# PhotoSensor.net
KiCad netlist of a schematic drawn in EAGLE
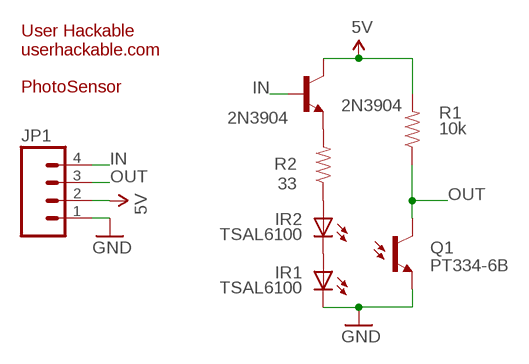
[diagram p0: schematic, sheet 1]

(export (version "E")
  (design (tool "Eeschema 10.0.6"))
  (components
    (comp (ref "2N3904")
      (value "2N3904")
      (footprint "eagle-import:TO-92-AMMO")
      (libsource (lib "eagle-import") (part "TRANSISTOR_NPNTO-92-AMMO"))
    )
    (comp (ref "IR1")
      (value "TSAL6100")
      (footprint "eagle-import:LED5MM")
      (libsource (lib "eagle-import") (part "LED5MM"))
    )
    (comp (ref "IR2")
      (value "TSAL6100")
      (footprint "eagle-import:LED5MM")
      (libsource (lib "eagle-import") (part "LED5MM"))
    )
    (comp (ref "JP1")
      (value "M04PTH")
      (footprint "eagle-import:1X04")
      (libsource (lib "eagle-import") (part "M04PTH"))
    )
    (comp (ref "Q1")
      (value "PT334-6B")
      (footprint "eagle-import:LED5MM")
      (libsource (lib "eagle-import") (part "PHOTOTRANSISTOR5MM"))
    )
    (comp (ref "R1")
      (value "10k")
      (footprint "eagle-import:AXIAL-0.3")
      (libsource (lib "eagle-import") (part "RESISTORAXIAL-0.3"))
    )
    (comp (ref "R2")
      (value "33")
      (footprint "eagle-import:AXIAL-0.3")
      (libsource (lib "eagle-import") (part "RESISTORAXIAL-0.3"))
    )
  )
  (nets
    (net (code "1") (name "/IN") (class "Default")
      (node (ref "2N3904") (pin "2") (pinfunction "B_2") (pintype "passive"))
      (node (ref "JP1") (pin "4") (pinfunction "4_4") (pintype "passive"))
    )
    (net (code "2") (name "/OUT") (class "Default")
      (node (ref "JP1") (pin "3") (pinfunction "3_3") (pintype "passive"))
      (node (ref "Q1") (pin "K") (pinfunction "C_K") (pintype "passive"))
      (node (ref "R1") (pin "P$1") (pinfunction "1_P$1") (pintype "passive"))
    )
    (net (code "3") (name "5V") (class "Default")
      (node (ref "2N3904") (pin "3") (pinfunction "C_3") (pintype "passive"))
      (node (ref "JP1") (pin "2") (pinfunction "2_2") (pintype "passive"))
      (node (ref "R1") (pin "P$2") (pinfunction "2_P$2") (pintype "passive"))
    )
    (net (code "4") (name "GND") (class "Default")
      (node (ref "IR1") (pin "K") (pinfunction "C_K") (pintype "passive"))
      (node (ref "JP1") (pin "1") (pinfunction "1_1") (pintype "passive"))
      (node (ref "Q1") (pin "A") (pinfunction "E_A") (pintype "passive"))
    )
    (net (code "5") (name "Net-(2N3904-E)") (class "Default")
      (node (ref "2N3904") (pin "1") (pinfunction "E_1") (pintype "passive"))
      (node (ref "R2") (pin "P$2") (pinfunction "2_P$2") (pintype "passive"))
    )
    (net (code "6") (name "Net-(IR2-C)") (class "Default")
      (node (ref "IR1") (pin "A") (pinfunction "A_A") (pintype "passive"))
      (node (ref "IR2") (pin "K") (pinfunction "C_K") (pintype "passive"))
    )
    (net (code "7") (name "Net-(R2-1)") (class "Default")
      (node (ref "IR2") (pin "A") (pinfunction "A_A") (pintype "passive"))
      (node (ref "R2") (pin "P$1") (pinfunction "1_P$1") (pintype "passive"))
    )
  )
)
